# VCO.net
KiCad netlist of a schematic drawn in Altium Designer
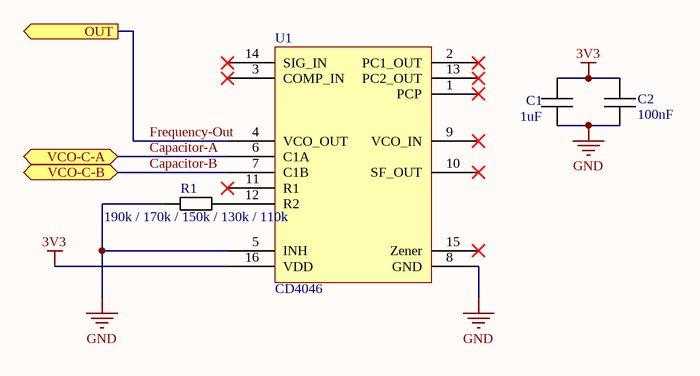
[diagram p0: VCO.SchDoc]

(export (version "E")
  (design (tool "Eeschema 10.0.6"))
  (components
    (comp (ref "C1")
      (value "1uF")
      (footprint "C 0805 / 2012")
      (libsource (lib "Standard") (part "Capacitor"))
    )
    (comp (ref "C2")
      (value "100nF")
      (footprint "C 0805 / 2012")
      (libsource (lib "Standard") (part "Capacitor"))
    )
    (comp (ref "R1")
      (value "190k / 170k / 150k / 130k / 110k")
      (footprint "R 0805 / 2012")
      (libsource (lib "Standard") (part "Resistor"))
    )
    (comp (ref "U1")
      (value "CD4046")
      (footprint "SOIC-16")
      (description "PLL / VCO")
      (libsource (lib "ICs") (part "CD4046"))
    )
  )
  (nets
    (net (code "1") (name "/Capacitor-A") (class "Default")
      (node (ref "U1") (pin "6") (pinfunction "C1A_6") (pintype "passive"))
    )
    (net (code "2") (name "/Capacitor-B") (class "Default")
      (node (ref "U1") (pin "7") (pinfunction "C1B_7") (pintype "passive"))
    )
    (net (code "3") (name "/Frequency-Out") (class "Default")
      (node (ref "U1") (pin "4") (pinfunction "VCO_OUT_4") (pintype "passive"))
    )
    (net (code "4") (name "3V3") (class "Default")
      (node (ref "C1") (pin "1") (pinfunction "1_1") (pintype "passive"))
      (node (ref "C2") (pin "1") (pinfunction "1_1") (pintype "passive"))
      (node (ref "U1") (pin "16") (pinfunction "VDD_16") (pintype "passive"))
    )
    (net (code "5") (name "GND") (class "Default")
      (node (ref "C1") (pin "2") (pinfunction "1_2") (pintype "passive"))
      (node (ref "C2") (pin "2") (pinfunction "1_2") (pintype "passive"))
      (node (ref "R1") (pin "2") (pinfunction "2_2") (pintype "passive"))
      (node (ref "U1") (pin "5") (pinfunction "INH_5") (pintype "passive"))
      (node (ref "U1") (pin "8") (pinfunction "GND_8") (pintype "passive"))
    )
    (net (code "6") (name "Net-(U1-R2)") (class "Default")
      (node (ref "R1") (pin "1") (pinfunction "1_1") (pintype "passive"))
      (node (ref "U1") (pin "12") (pinfunction "R2_12") (pintype "passive"))
    )
    (net (code "7") (name "unconnected-(U1-COMP_IN-Pad3)") (class "Default")
      (node (ref "U1") (pin "3") (pinfunction "COMP_IN_3") (pintype "passive+no_connect"))
    )
    (net (code "8") (name "unconnected-(U1-PC1_OUT-Pad2)") (class "Default")
      (node (ref "U1") (pin "2") (pinfunction "PC1_OUT_2") (pintype "passive+no_connect"))
    )
    (net (code "9") (name "unconnected-(U1-PC2_OUT-Pad13)") (class "Default")
      (node (ref "U1") (pin "13") (pinfunction "PC2_OUT_13") (pintype "passive+no_connect"))
    )
    (net (code "10") (name "unconnected-(U1-PCP-Pad1)") (class "Default")
      (node (ref "U1") (pin "1") (pinfunction "PCP_1") (pintype "passive+no_connect"))
    )
    (net (code "11") (name "unconnected-(U1-R1-Pad11)") (class "Default")
      (node (ref "U1") (pin "11") (pinfunction "R1_11") (pintype "passive+no_connect"))
    )
    (net (code "12") (name "unconnected-(U1-SF_OUT-Pad10)") (class "Default")
      (node (ref "U1") (pin "10") (pinfunction "SF_OUT_10") (pintype "passive+no_connect"))
    )
    (net (code "13") (name "unconnected-(U1-SIG_IN-Pad14)") (class "Default")
      (node (ref "U1") (pin "14") (pinfunction "SIG_IN_14") (pintype "passive+no_connect"))
    )
    (net (code "14") (name "unconnected-(U1-VCO_IN-Pad9)") (class "Default")
      (node (ref "U1") (pin "9") (pinfunction "VCO_IN_9") (pintype "passive+no_connect"))
    )
    (net (code "15") (name "unconnected-(U1-Zener-Pad15)") (class "Default")
      (node (ref "U1") (pin "15") (pinfunction "Zener_15") (pintype "passive+no_connect"))
    )
  )
)
